# Power-Monitor-Module.net
KiCad netlist of a schematic drawn in EAGLE
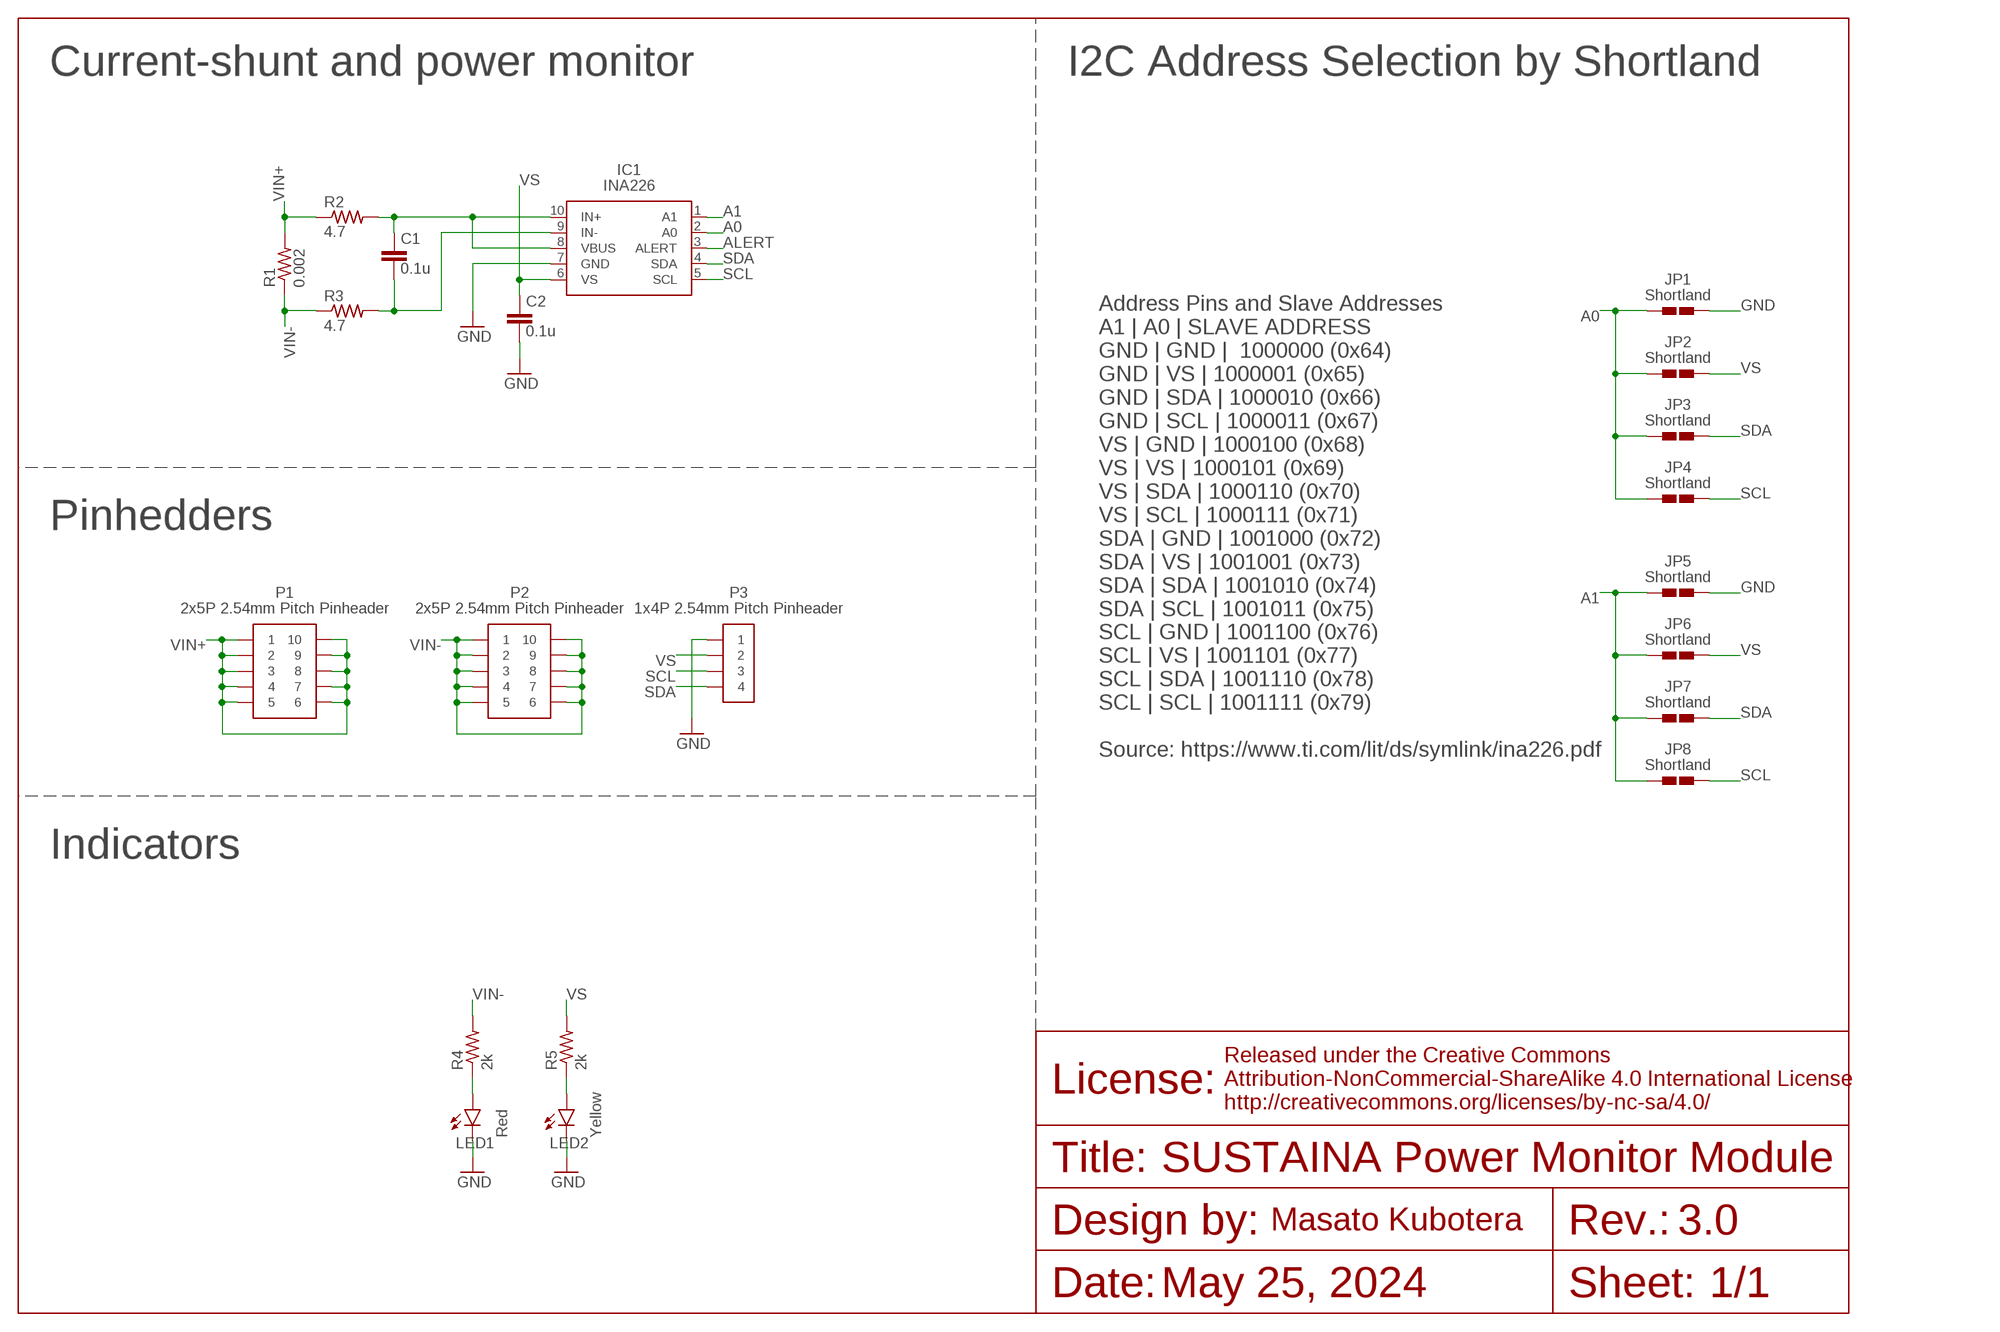
[diagram p0: schematic, sheet 1]

(export (version "E")
  (design (tool "Eeschema 10.0.6"))
  (components
    (comp (ref "C1")
      (value "0.1u")
      (footprint "eagle-import:C0402")
      (libsource (lib "eagle-import") (part "C-EUC0402"))
    )
    (comp (ref "C2")
      (value "0.1u")
      (footprint "eagle-import:C0402")
      (libsource (lib "eagle-import") (part "C-EUC0402"))
    )
    (comp (ref "IC1")
      (value "INA226")
      (footprint "eagle-import:MSOP-10")
      (libsource (lib "eagle-import") (part "INA226"))
    )
    (comp (ref "JP1")
      (value "SHORTLAND")
      (footprint "eagle-import:SHORTLAND")
      (libsource (lib "eagle-import") (part "SHORTLAND"))
    )
    (comp (ref "JP2")
      (value "SHORTLAND")
      (footprint "eagle-import:SHORTLAND")
      (libsource (lib "eagle-import") (part "SHORTLAND"))
    )
    (comp (ref "JP3")
      (value "SHORTLAND")
      (footprint "eagle-import:SHORTLAND")
      (libsource (lib "eagle-import") (part "SHORTLAND"))
    )
    (comp (ref "JP4")
      (value "SHORTLAND")
      (footprint "eagle-import:SHORTLAND")
      (libsource (lib "eagle-import") (part "SHORTLAND"))
    )
    (comp (ref "JP5")
      (value "SHORTLAND")
      (footprint "eagle-import:SHORTLAND")
      (libsource (lib "eagle-import") (part "SHORTLAND"))
    )
    (comp (ref "JP6")
      (value "SHORTLAND")
      (footprint "eagle-import:SHORTLAND")
      (libsource (lib "eagle-import") (part "SHORTLAND"))
    )
    (comp (ref "JP7")
      (value "SHORTLAND")
      (footprint "eagle-import:SHORTLAND")
      (libsource (lib "eagle-import") (part "SHORTLAND"))
    )
    (comp (ref "JP8")
      (value "SHORTLAND")
      (footprint "eagle-import:SHORTLAND")
      (libsource (lib "eagle-import") (part "SHORTLAND"))
    )
    (comp (ref "LED1")
      (value "Red")
      (footprint "eagle-import:SML0603")
      (libsource (lib "eagle-import") (part "LEDSML0603"))
    )
    (comp (ref "LED2")
      (value "Yellow")
      (footprint "eagle-import:SML0603")
      (libsource (lib "eagle-import") (part "LEDSML0603"))
    )
    (comp (ref "P1")
      (value "2X5P")
      (footprint "eagle-import:2X5P")
      (libsource (lib "eagle-import") (part "2X5P"))
    )
    (comp (ref "P2")
      (value "2X5P")
      (footprint "eagle-import:2X5P")
      (libsource (lib "eagle-import") (part "2X5P"))
    )
    (comp (ref "P3")
      (value "1X4P")
      (footprint "eagle-import:1X4P")
      (libsource (lib "eagle-import") (part "1X4P"))
    )
    (comp (ref "R1")
      (value "0.002")
      (footprint "eagle-import:R2512")
      (libsource (lib "eagle-import") (part "R-US_R2512"))
    )
    (comp (ref "R2")
      (value "4.7")
      (footprint "eagle-import:R0402")
      (libsource (lib "eagle-import") (part "R-US_R0402"))
    )
    (comp (ref "R3")
      (value "4.7")
      (footprint "eagle-import:R0402")
      (libsource (lib "eagle-import") (part "R-US_R0402"))
    )
    (comp (ref "R4")
      (value "2k")
      (footprint "eagle-import:R0402")
      (libsource (lib "eagle-import") (part "R-US_R0402"))
    )
    (comp (ref "R5")
      (value "2k")
      (footprint "eagle-import:R0402")
      (libsource (lib "eagle-import") (part "R-US_R0402"))
    )
  )
  (nets
    (net (code "1") (name "/A0") (class "Default")
      (node (ref "IC1") (pin "2") (pinfunction "A0_2") (pintype "bidirectional"))
      (node (ref "JP1") (pin "1") (pinfunction "1_1") (pintype "bidirectional"))
      (node (ref "JP2") (pin "1") (pinfunction "1_1") (pintype "bidirectional"))
      (node (ref "JP3") (pin "1") (pinfunction "1_1") (pintype "bidirectional"))
      (node (ref "JP4") (pin "1") (pinfunction "1_1") (pintype "bidirectional"))
    )
    (net (code "2") (name "/A1") (class "Default")
      (node (ref "IC1") (pin "1") (pinfunction "A1_1") (pintype "bidirectional"))
      (node (ref "JP5") (pin "1") (pinfunction "1_1") (pintype "bidirectional"))
      (node (ref "JP6") (pin "1") (pinfunction "1_1") (pintype "bidirectional"))
      (node (ref "JP7") (pin "1") (pinfunction "1_1") (pintype "bidirectional"))
      (node (ref "JP8") (pin "1") (pinfunction "1_1") (pintype "bidirectional"))
    )
    (net (code "3") (name "/ALERT") (class "Default")
      (node (ref "IC1") (pin "3") (pinfunction "ALERT_3") (pintype "bidirectional"))
    )
    (net (code "4") (name "/SCL") (class "Default")
      (node (ref "IC1") (pin "5") (pinfunction "SCL_5") (pintype "bidirectional"))
      (node (ref "JP4") (pin "2") (pinfunction "2_2") (pintype "bidirectional"))
      (node (ref "JP8") (pin "2") (pinfunction "2_2") (pintype "bidirectional"))
      (node (ref "P3") (pin "3") (pinfunction "3_3") (pintype "bidirectional"))
    )
    (net (code "5") (name "/SDA") (class "Default")
      (node (ref "IC1") (pin "4") (pinfunction "SDA_4") (pintype "bidirectional"))
      (node (ref "JP3") (pin "2") (pinfunction "2_2") (pintype "bidirectional"))
      (node (ref "JP7") (pin "2") (pinfunction "2_2") (pintype "bidirectional"))
      (node (ref "P3") (pin "4") (pinfunction "4_4") (pintype "bidirectional"))
    )
    (net (code "6") (name "/VIN+") (class "Default")
      (node (ref "P1") (pin "1") (pinfunction "1_1") (pintype "bidirectional"))
      (node (ref "P1") (pin "10") (pinfunction "10_10") (pintype "bidirectional"))
      (node (ref "P1") (pin "2") (pinfunction "2_2") (pintype "bidirectional"))
      (node (ref "P1") (pin "3") (pinfunction "3_3") (pintype "bidirectional"))
      (node (ref "P1") (pin "4") (pinfunction "4_4") (pintype "bidirectional"))
      (node (ref "P1") (pin "5") (pinfunction "5_5") (pintype "bidirectional"))
      (node (ref "P1") (pin "6") (pinfunction "6_6") (pintype "bidirectional"))
      (node (ref "P1") (pin "7") (pinfunction "7_7") (pintype "bidirectional"))
      (node (ref "P1") (pin "8") (pinfunction "8_8") (pintype "bidirectional"))
      (node (ref "P1") (pin "9") (pinfunction "9_9") (pintype "bidirectional"))
      (node (ref "R1") (pin "2") (pinfunction "2_2") (pintype "passive"))
      (node (ref "R2") (pin "1") (pinfunction "1_1") (pintype "passive"))
    )
    (net (code "7") (name "/VIN-") (class "Default")
      (node (ref "P2") (pin "1") (pinfunction "1_1") (pintype "bidirectional"))
      (node (ref "P2") (pin "10") (pinfunction "10_10") (pintype "bidirectional"))
      (node (ref "P2") (pin "2") (pinfunction "2_2") (pintype "bidirectional"))
      (node (ref "P2") (pin "3") (pinfunction "3_3") (pintype "bidirectional"))
      (node (ref "P2") (pin "4") (pinfunction "4_4") (pintype "bidirectional"))
      (node (ref "P2") (pin "5") (pinfunction "5_5") (pintype "bidirectional"))
      (node (ref "P2") (pin "6") (pinfunction "6_6") (pintype "bidirectional"))
      (node (ref "P2") (pin "7") (pinfunction "7_7") (pintype "bidirectional"))
      (node (ref "P2") (pin "8") (pinfunction "8_8") (pintype "bidirectional"))
      (node (ref "P2") (pin "9") (pinfunction "9_9") (pintype "bidirectional"))
      (node (ref "R1") (pin "1") (pinfunction "1_1") (pintype "passive"))
      (node (ref "R3") (pin "1") (pinfunction "1_1") (pintype "passive"))
      (node (ref "R4") (pin "2") (pinfunction "2_2") (pintype "passive"))
    )
    (net (code "8") (name "/VS") (class "Default")
      (node (ref "C2") (pin "1") (pinfunction "1_1") (pintype "passive"))
      (node (ref "IC1") (pin "6") (pinfunction "VS_6") (pintype "bidirectional"))
      (node (ref "JP2") (pin "2") (pinfunction "2_2") (pintype "bidirectional"))
      (node (ref "JP6") (pin "2") (pinfunction "2_2") (pintype "bidirectional"))
      (node (ref "P3") (pin "2") (pinfunction "2_2") (pintype "bidirectional"))
      (node (ref "R5") (pin "2") (pinfunction "2_2") (pintype "passive"))
    )
    (net (code "9") (name "GND") (class "Default")
      (node (ref "C2") (pin "2") (pinfunction "2_2") (pintype "passive"))
      (node (ref "IC1") (pin "7") (pinfunction "GND_7") (pintype "bidirectional"))
      (node (ref "JP1") (pin "2") (pinfunction "2_2") (pintype "bidirectional"))
      (node (ref "JP5") (pin "2") (pinfunction "2_2") (pintype "bidirectional"))
      (node (ref "LED1") (pin "C") (pinfunction "C_C") (pintype "passive"))
      (node (ref "LED2") (pin "C") (pinfunction "C_C") (pintype "passive"))
      (node (ref "P3") (pin "1") (pinfunction "1_1") (pintype "bidirectional"))
    )
    (net (code "10") (name "Net-(IC1-IN+)") (class "Default")
      (node (ref "C1") (pin "1") (pinfunction "1_1") (pintype "passive"))
      (node (ref "IC1") (pin "10") (pinfunction "IN+_10") (pintype "bidirectional"))
      (node (ref "IC1") (pin "8") (pinfunction "VBUS_8") (pintype "bidirectional"))
      (node (ref "R2") (pin "2") (pinfunction "2_2") (pintype "passive"))
    )
    (net (code "11") (name "Net-(IC1-IN-)") (class "Default")
      (node (ref "C1") (pin "2") (pinfunction "2_2") (pintype "passive"))
      (node (ref "IC1") (pin "9") (pinfunction "IN-_9") (pintype "bidirectional"))
      (node (ref "R3") (pin "2") (pinfunction "2_2") (pintype "passive"))
    )
    (net (code "12") (name "Net-(LED1-PadA)") (class "Default")
      (node (ref "LED1") (pin "A") (pinfunction "A_A") (pintype "passive"))
      (node (ref "R4") (pin "1") (pinfunction "1_1") (pintype "passive"))
    )
    (net (code "13") (name "Net-(LED2-PadA)") (class "Default")
      (node (ref "LED2") (pin "A") (pinfunction "A_A") (pintype "passive"))
      (node (ref "R5") (pin "1") (pinfunction "1_1") (pintype "passive"))
    )
  )
)
